# SCH_PCB-BRAILLE_2026-08-12.net
KiCad netlist of a schematic drawn in EasyEDA
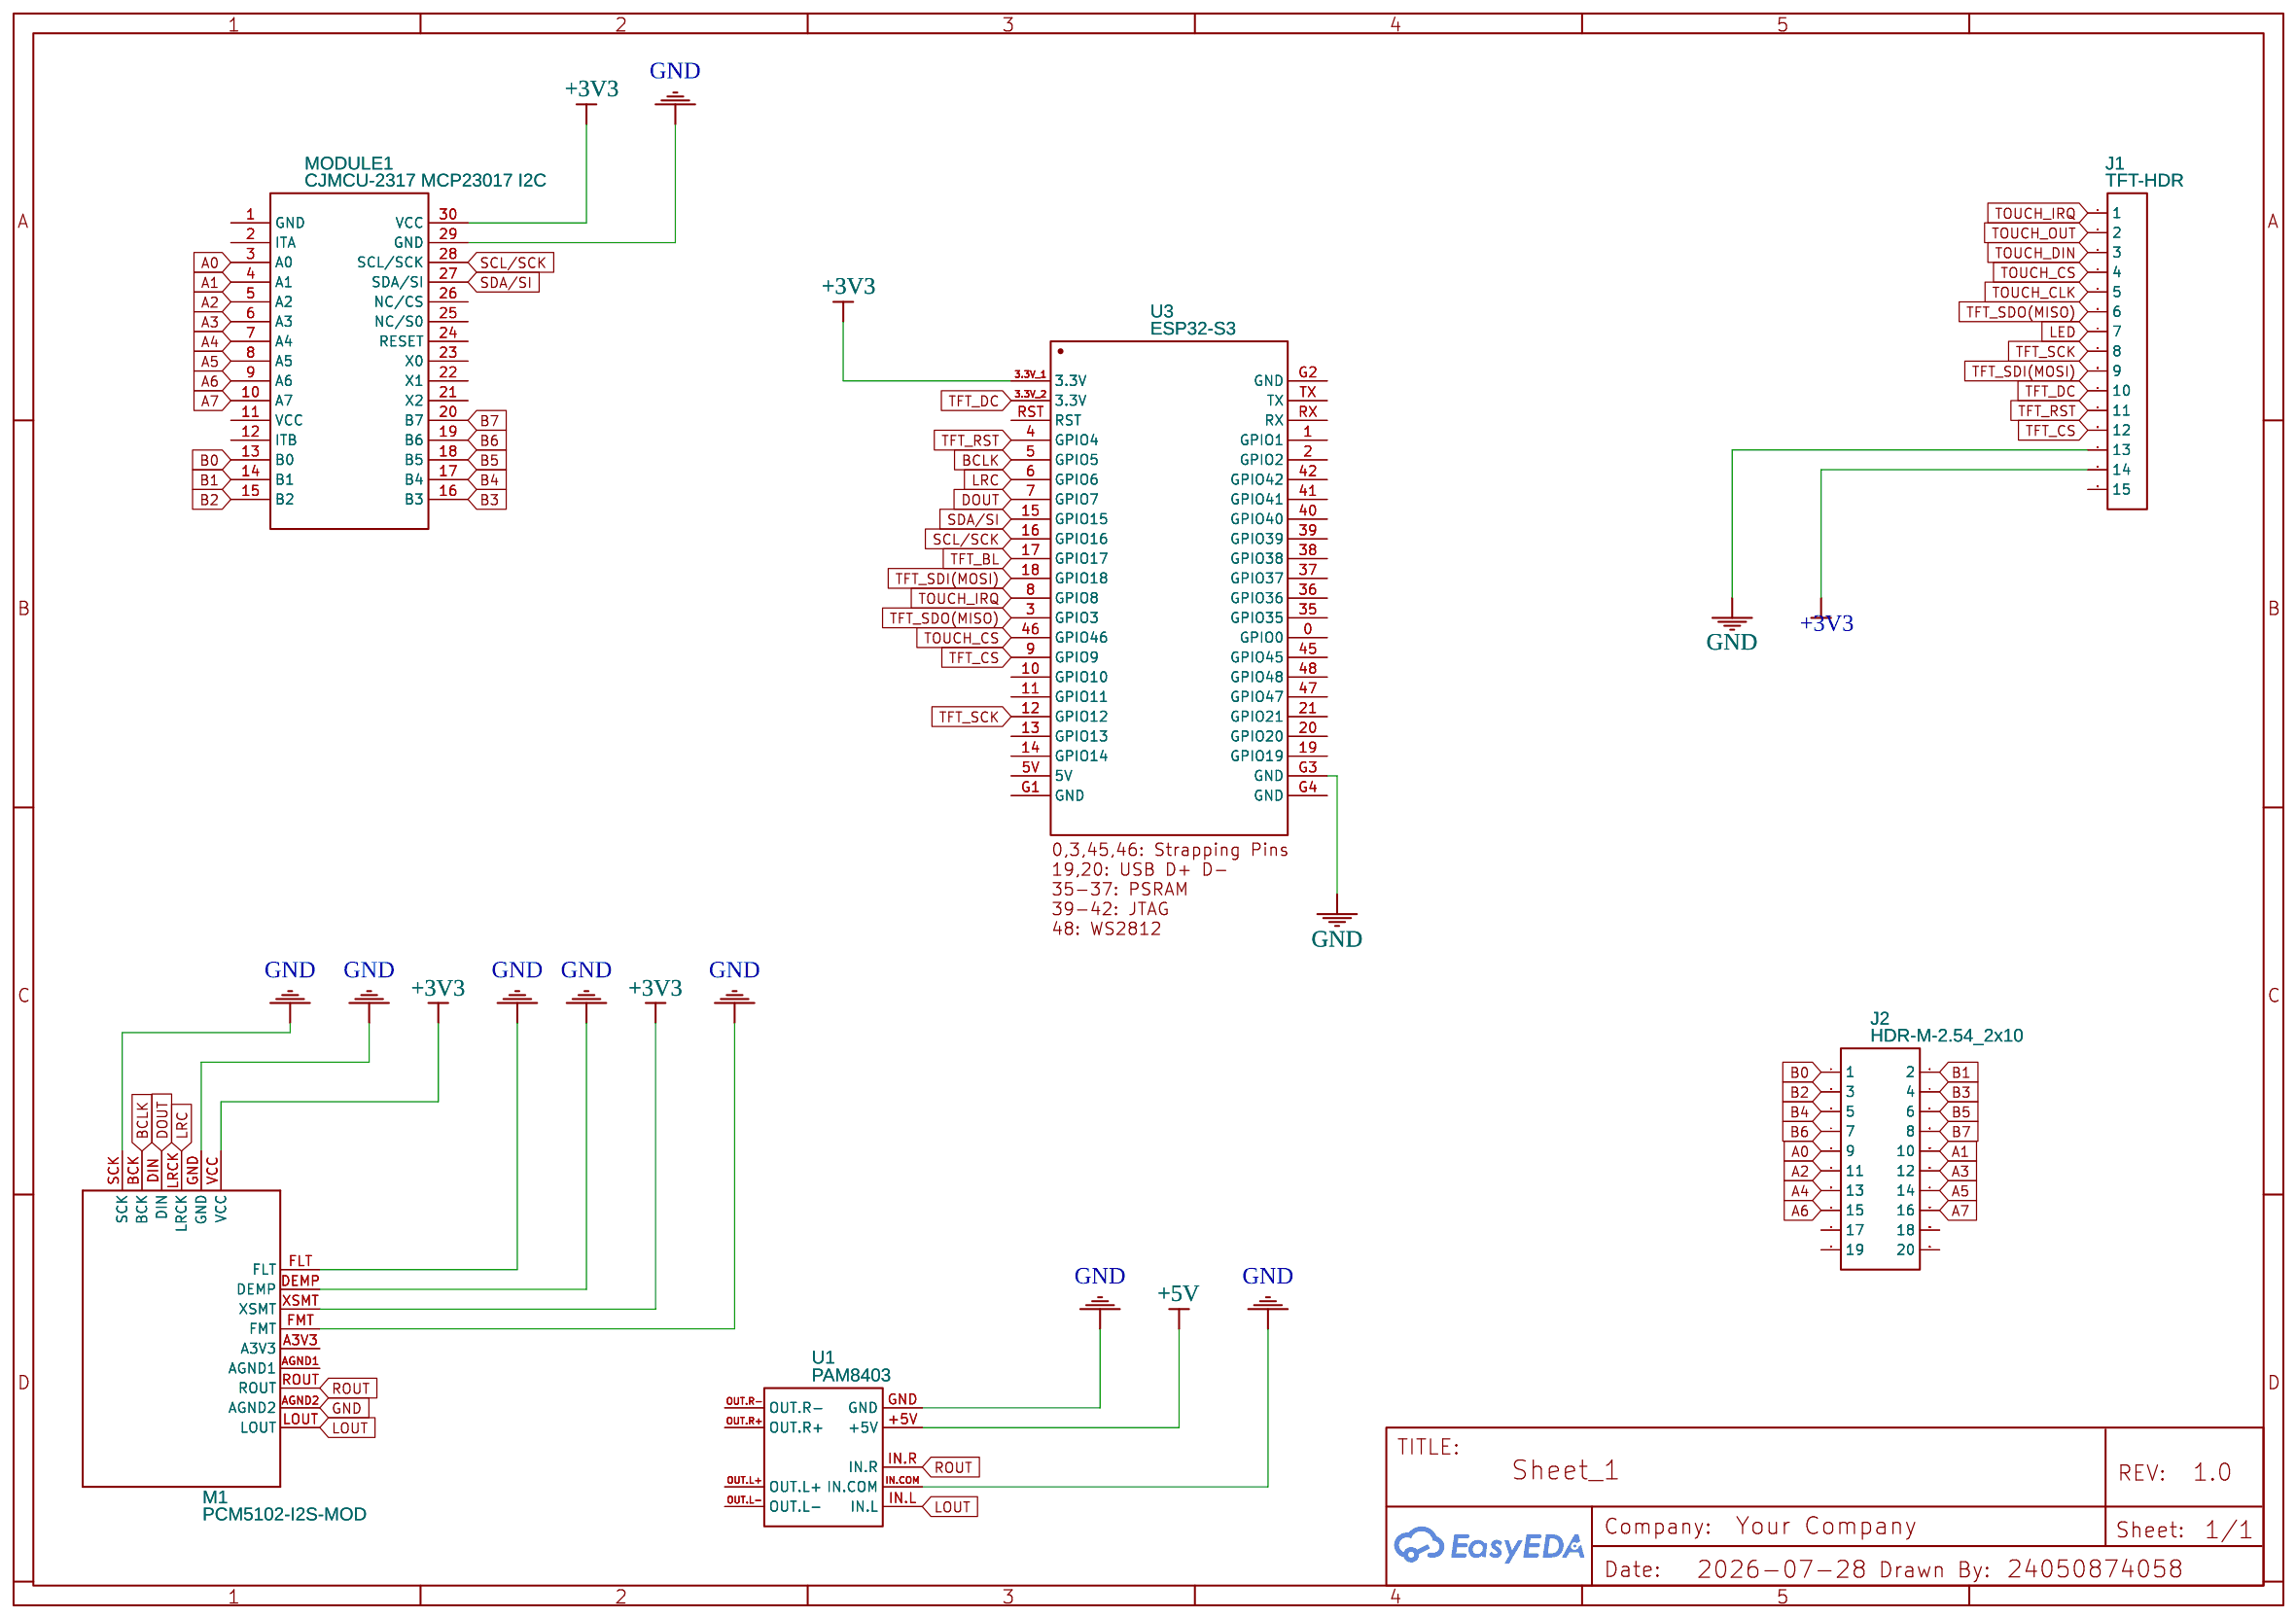
[diagram p0: schematic sheet]

(export (version "E")
  (design (tool "Eeschema 10.0.6"))
  (components
    (comp (ref "J1") (value "TFT-HDR") (libsource (lib "") (part "HDR-M-2.54_1x15")))
    (comp (ref "J2") (value "HDR-M-2.54_2x10") (libsource (lib "") (part "HDR-M-2.54_2x10")))
    (comp (ref "M1") (value "PCM5102-I2S-MOD") (libsource (lib "") (part "PCM5102-I2S-MOD")))
    (comp (ref "MODULE1")
      (value "CJMCU-2317 MCP23017 I2C")
      (libsource (lib "") (part "CJMCU-2317 MCP23017 I2C Serial Interface 16 bit I/O Expander Serial Module"))
    )
    (comp (ref "U1") (value "PAM8403") (libsource (lib "") (part "PAM8403")))
    (comp (ref "U3") (value "ESP32-S3") (libsource (lib "") (part "ESP32-S3")))
  )
  (nets
    (net (code "1") (name "+3V3") (class "Default")
      (node (ref "J1") (pin "14") (pinfunction "14_14") (pintype "unspecified"))
      (node (ref "M1") (pin "VCC") (pinfunction "VCC_VCC") (pintype "bidirectional"))
      (node (ref "M1") (pin "XSMT") (pinfunction "XSMT_XSMT") (pintype "bidirectional"))
      (node (ref "MODULE1") (pin "30") (pinfunction "VCC_30") (pintype "unspecified"))
      (node (ref "U3") (pin "3.3V_1") (pinfunction "3.3V_3.3V_1") (pintype "bidirectional"))
    )
    (net (code "2") (name "+5V") (class "Default")
      (node (ref "U1") (pin "+5V") (pinfunction "+5V_+5V") (pintype "unspecified"))
    )
    (net (code "3") (name "A0") (class "Default")
      (node (ref "J2") (pin "9") (pinfunction "9_9") (pintype "unspecified"))
      (node (ref "MODULE1") (pin "3") (pinfunction "A0_3") (pintype "unspecified"))
    )
    (net (code "4") (name "A1") (class "Default")
      (node (ref "J2") (pin "10") (pinfunction "10_10") (pintype "unspecified"))
      (node (ref "MODULE1") (pin "4") (pinfunction "A1_4") (pintype "unspecified"))
    )
    (net (code "5") (name "A2") (class "Default")
      (node (ref "J2") (pin "11") (pinfunction "11_11") (pintype "unspecified"))
      (node (ref "MODULE1") (pin "5") (pinfunction "A2_5") (pintype "unspecified"))
    )
    (net (code "6") (name "A3") (class "Default")
      (node (ref "J2") (pin "12") (pinfunction "12_12") (pintype "unspecified"))
      (node (ref "MODULE1") (pin "6") (pinfunction "A3_6") (pintype "unspecified"))
    )
    (net (code "7") (name "A4") (class "Default")
      (node (ref "J2") (pin "13") (pinfunction "13_13") (pintype "unspecified"))
      (node (ref "MODULE1") (pin "7") (pinfunction "A4_7") (pintype "unspecified"))
    )
    (net (code "8") (name "A5") (class "Default")
      (node (ref "J2") (pin "14") (pinfunction "14_14") (pintype "unspecified"))
      (node (ref "MODULE1") (pin "8") (pinfunction "A5_8") (pintype "unspecified"))
    )
    (net (code "9") (name "A6") (class "Default")
      (node (ref "J2") (pin "15") (pinfunction "15_15") (pintype "unspecified"))
      (node (ref "MODULE1") (pin "9") (pinfunction "A6_9") (pintype "unspecified"))
    )
    (net (code "10") (name "A7") (class "Default")
      (node (ref "J2") (pin "16") (pinfunction "16_16") (pintype "unspecified"))
      (node (ref "MODULE1") (pin "10") (pinfunction "A7_10") (pintype "unspecified"))
    )
    (net (code "11") (name "B0") (class "Default")
      (node (ref "J2") (pin "1") (pinfunction "1_1") (pintype "unspecified"))
      (node (ref "MODULE1") (pin "13") (pinfunction "B0_13") (pintype "unspecified"))
    )
    (net (code "12") (name "B1") (class "Default")
      (node (ref "J2") (pin "2") (pinfunction "2_2") (pintype "unspecified"))
      (node (ref "MODULE1") (pin "14") (pinfunction "B1_14") (pintype "unspecified"))
    )
    (net (code "13") (name "B2") (class "Default")
      (node (ref "J2") (pin "3") (pinfunction "3_3") (pintype "unspecified"))
      (node (ref "MODULE1") (pin "15") (pinfunction "B2_15") (pintype "unspecified"))
    )
    (net (code "14") (name "B3") (class "Default")
      (node (ref "J2") (pin "4") (pinfunction "4_4") (pintype "unspecified"))
      (node (ref "MODULE1") (pin "16") (pinfunction "B3_16") (pintype "unspecified"))
    )
    (net (code "15") (name "B4") (class "Default")
      (node (ref "J2") (pin "5") (pinfunction "5_5") (pintype "unspecified"))
      (node (ref "MODULE1") (pin "17") (pinfunction "B4_17") (pintype "unspecified"))
    )
    (net (code "16") (name "B5") (class "Default")
      (node (ref "J2") (pin "6") (pinfunction "6_6") (pintype "unspecified"))
      (node (ref "MODULE1") (pin "18") (pinfunction "B5_18") (pintype "unspecified"))
    )
    (net (code "17") (name "B6") (class "Default")
      (node (ref "J2") (pin "7") (pinfunction "7_7") (pintype "unspecified"))
      (node (ref "MODULE1") (pin "19") (pinfunction "B6_19") (pintype "unspecified"))
    )
    (net (code "18") (name "B7") (class "Default")
      (node (ref "J2") (pin "8") (pinfunction "8_8") (pintype "unspecified"))
      (node (ref "MODULE1") (pin "20") (pinfunction "B7_20") (pintype "unspecified"))
    )
    (net (code "19") (name "BCLK") (class "Default")
      (node (ref "M1") (pin "BCK") (pinfunction "BCK_BCK") (pintype "bidirectional"))
      (node (ref "U3") (pin "5") (pinfunction "GPIO5_5") (pintype "bidirectional"))
    )
    (net (code "20") (name "DOUT") (class "Default")
      (node (ref "M1") (pin "DIN") (pinfunction "DIN_DIN") (pintype "bidirectional"))
      (node (ref "U3") (pin "7") (pinfunction "GPIO7_7") (pintype "bidirectional"))
    )
    (net (code "21") (name "GND") (class "Default")
      (node (ref "J1") (pin "13") (pinfunction "13_13") (pintype "unspecified"))
      (node (ref "M1") (pin "AGND2") (pinfunction "AGND2_AGND2") (pintype "bidirectional"))
      (node (ref "M1") (pin "DEMP") (pinfunction "DEMP_DEMP") (pintype "bidirectional"))
      (node (ref "M1") (pin "FLT") (pinfunction "FLT_FLT") (pintype "bidirectional"))
      (node (ref "M1") (pin "FMT") (pinfunction "FMT_FMT") (pintype "bidirectional"))
      (node (ref "M1") (pin "GND") (pinfunction "GND_GND") (pintype "bidirectional"))
      (node (ref "M1") (pin "SCK") (pinfunction "SCK_SCK") (pintype "bidirectional"))
      (node (ref "MODULE1") (pin "29") (pinfunction "GND_29") (pintype "unspecified"))
      (node (ref "U1") (pin "GND") (pinfunction "GND_GND") (pintype "unspecified"))
      (node (ref "U1") (pin "IN.COM") (pinfunction "IN.COM_IN.COM") (pintype "unspecified"))
      (node (ref "U3") (pin "G3") (pinfunction "GND_G3") (pintype "bidirectional"))
    )
    (net (code "22") (name "LED") (class "Default")
      (node (ref "J1") (pin "7") (pinfunction "7_7") (pintype "unspecified"))
    )
    (net (code "23") (name "LOUT") (class "Default")
      (node (ref "M1") (pin "LOUT") (pinfunction "LOUT_LOUT") (pintype "bidirectional"))
      (node (ref "U1") (pin "IN.L") (pinfunction "IN.L_IN.L") (pintype "unspecified"))
    )
    (net (code "24") (name "LRC") (class "Default")
      (node (ref "M1") (pin "LRCK") (pinfunction "LRCK_LRCK") (pintype "bidirectional"))
      (node (ref "U3") (pin "6") (pinfunction "GPIO6_6") (pintype "bidirectional"))
    )
    (net (code "25") (name "ROUT") (class "Default")
      (node (ref "M1") (pin "ROUT") (pinfunction "ROUT_ROUT") (pintype "bidirectional"))
      (node (ref "U1") (pin "IN.R") (pinfunction "IN.R_IN.R") (pintype "unspecified"))
    )
    (net (code "26") (name "SCL{slash}SCK") (class "Default")
      (node (ref "MODULE1") (pin "28") (pinfunction "SCL/SCK_28") (pintype "unspecified"))
      (node (ref "U3") (pin "16") (pinfunction "GPIO16_16") (pintype "bidirectional"))
    )
    (net (code "27") (name "SDA{slash}SI") (class "Default")
      (node (ref "MODULE1") (pin "27") (pinfunction "SDA/SI_27") (pintype "unspecified"))
      (node (ref "U3") (pin "15") (pinfunction "GPIO15_15") (pintype "bidirectional"))
    )
    (net (code "28") (name "TFT_BL") (class "Default")
      (node (ref "U3") (pin "17") (pinfunction "GPIO17_17") (pintype "bidirectional"))
    )
    (net (code "29") (name "TFT_CS") (class "Default")
      (node (ref "J1") (pin "12") (pinfunction "12_12") (pintype "unspecified"))
      (node (ref "U3") (pin "9") (pinfunction "GPIO9_9") (pintype "bidirectional"))
    )
    (net (code "30") (name "TFT_DC") (class "Default")
      (node (ref "J1") (pin "10") (pinfunction "10_10") (pintype "unspecified"))
      (node (ref "U3") (pin "3.3V_2") (pinfunction "3.3V_3.3V_2") (pintype "bidirectional"))
    )
    (net (code "31") (name "TFT_RST") (class "Default")
      (node (ref "J1") (pin "11") (pinfunction "11_11") (pintype "unspecified"))
      (node (ref "U3") (pin "4") (pinfunction "GPIO4_4") (pintype "bidirectional"))
    )
    (net (code "32") (name "TFT_SCK") (class "Default")
      (node (ref "J1") (pin "8") (pinfunction "8_8") (pintype "unspecified"))
      (node (ref "U3") (pin "12") (pinfunction "GPIO12_12") (pintype "bidirectional"))
    )
    (net (code "33") (name "TFT_SDI(MOSI)") (class "Default")
      (node (ref "J1") (pin "9") (pinfunction "9_9") (pintype "unspecified"))
      (node (ref "U3") (pin "18") (pinfunction "GPIO18_18") (pintype "bidirectional"))
    )
    (net (code "34") (name "TFT_SDO(MISO)") (class "Default")
      (node (ref "J1") (pin "6") (pinfunction "6_6") (pintype "unspecified"))
      (node (ref "U3") (pin "3") (pinfunction "GPIO3_3") (pintype "bidirectional"))
    )
    (net (code "35") (name "TOUCH_CLK") (class "Default")
      (node (ref "J1") (pin "5") (pinfunction "5_5") (pintype "unspecified"))
    )
    (net (code "36") (name "TOUCH_CS") (class "Default")
      (node (ref "J1") (pin "4") (pinfunction "4_4") (pintype "unspecified"))
      (node (ref "U3") (pin "46") (pinfunction "GPIO46_46") (pintype "bidirectional"))
    )
    (net (code "37") (name "TOUCH_DIN") (class "Default")
      (node (ref "J1") (pin "3") (pinfunction "3_3") (pintype "unspecified"))
    )
    (net (code "38") (name "TOUCH_IRQ") (class "Default")
      (node (ref "J1") (pin "1") (pinfunction "1_1") (pintype "unspecified"))
      (node (ref "U3") (pin "8") (pinfunction "GPIO8_8") (pintype "bidirectional"))
    )
    (net (code "39") (name "TOUCH_OUT") (class "Default")
      (node (ref "J1") (pin "2") (pinfunction "2_2") (pintype "unspecified"))
    )
    (net (code "40") (name "unconnected-(J1-Pad15)") (class "Default")
      (node (ref "J1") (pin "15") (pinfunction "15_15") (pintype "unspecified"))
    )
    (net (code "41") (name "unconnected-(J2-Pad17)") (class "Default")
      (node (ref "J2") (pin "17") (pinfunction "17_17") (pintype "unspecified"))
    )
    (net (code "42") (name "unconnected-(J2-Pad18)") (class "Default")
      (node (ref "J2") (pin "18") (pinfunction "18_18") (pintype "unspecified"))
    )
    (net (code "43") (name "unconnected-(J2-Pad19)") (class "Default")
      (node (ref "J2") (pin "19") (pinfunction "19_19") (pintype "unspecified"))
    )
    (net (code "44") (name "unconnected-(J2-Pad20)") (class "Default")
      (node (ref "J2") (pin "20") (pinfunction "20_20") (pintype "unspecified"))
    )
    (net (code "45") (name "unconnected-(M1-PadA3V3)") (class "Default")
      (node (ref "M1") (pin "A3V3") (pinfunction "A3V3_A3V3") (pintype "bidirectional"))
    )
    (net (code "46") (name "unconnected-(M1-PadAGND1)") (class "Default")
      (node (ref "M1") (pin "AGND1") (pinfunction "AGND1_AGND1") (pintype "bidirectional"))
    )
    (net (code "47") (name "unconnected-(MODULE1-GND-Pad1)") (class "Default")
      (node (ref "MODULE1") (pin "1") (pinfunction "GND_1") (pintype "unspecified"))
    )
    (net (code "48") (name "unconnected-(MODULE1-ITA-Pad2)") (class "Default")
      (node (ref "MODULE1") (pin "2") (pinfunction "ITA_2") (pintype "unspecified"))
    )
    (net (code "49") (name "unconnected-(MODULE1-ITB-Pad12)") (class "Default")
      (node (ref "MODULE1") (pin "12") (pinfunction "ITB_12") (pintype "unspecified"))
    )
    (net (code "50") (name "unconnected-(MODULE1-NC{slash}CS-Pad26)") (class "Default")
      (node (ref "MODULE1") (pin "26") (pinfunction "NC/CS_26") (pintype "unspecified"))
    )
    (net (code "51") (name "unconnected-(MODULE1-NC{slash}S0-Pad25)") (class "Default")
      (node (ref "MODULE1") (pin "25") (pinfunction "NC/S0_25") (pintype "unspecified"))
    )
    (net (code "52") (name "unconnected-(MODULE1-RESET-Pad24)") (class "Default")
      (node (ref "MODULE1") (pin "24") (pinfunction "RESET_24") (pintype "unspecified"))
    )
    (net (code "53") (name "unconnected-(MODULE1-VCC-Pad11)") (class "Default")
      (node (ref "MODULE1") (pin "11") (pinfunction "VCC_11") (pintype "unspecified"))
    )
    (net (code "54") (name "unconnected-(MODULE1-X0-Pad23)") (class "Default")
      (node (ref "MODULE1") (pin "23") (pinfunction "X0_23") (pintype "unspecified"))
    )
    (net (code "55") (name "unconnected-(MODULE1-X1-Pad22)") (class "Default")
      (node (ref "MODULE1") (pin "22") (pinfunction "X1_22") (pintype "unspecified"))
    )
    (net (code "56") (name "unconnected-(MODULE1-X2-Pad21)") (class "Default")
      (node (ref "MODULE1") (pin "21") (pinfunction "X2_21") (pintype "unspecified"))
    )
    (net (code "57") (name "unconnected-(U1-PadOUT.L+)") (class "Default")
      (node (ref "U1") (pin "OUT.L+") (pinfunction "OUT.L+_OUT.L+") (pintype "unspecified"))
    )
    (net (code "58") (name "unconnected-(U1-PadOUT.L-)") (class "Default")
      (node (ref "U1") (pin "OUT.L-") (pinfunction "OUT.L-_OUT.L-") (pintype "unspecified"))
    )
    (net (code "59") (name "unconnected-(U1-PadOUT.R+)") (class "Default")
      (node (ref "U1") (pin "OUT.R+") (pinfunction "OUT.R+_OUT.R+") (pintype "unspecified"))
    )
    (net (code "60") (name "unconnected-(U1-PadOUT.R-)") (class "Default")
      (node (ref "U1") (pin "OUT.R-") (pinfunction "OUT.R-_OUT.R-") (pintype "unspecified"))
    )
    (net (code "61") (name "unconnected-(U3-GND-PadG1)") (class "Default")
      (node (ref "U3") (pin "G1") (pinfunction "GND_G1") (pintype "bidirectional"))
    )
    (net (code "62") (name "unconnected-(U3-GND-PadG2)") (class "Default")
      (node (ref "U3") (pin "G2") (pinfunction "GND_G2") (pintype "bidirectional"))
    )
    (net (code "63") (name "unconnected-(U3-GND-PadG4)") (class "Default")
      (node (ref "U3") (pin "G4") (pinfunction "GND_G4") (pintype "bidirectional"))
    )
    (net (code "64") (name "unconnected-(U3-GPIO0-Pad0)") (class "Default")
      (node (ref "U3") (pin "0") (pinfunction "GPIO0_0") (pintype "bidirectional"))
    )
    (net (code "65") (name "unconnected-(U3-GPIO1-Pad1)") (class "Default")
      (node (ref "U3") (pin "1") (pinfunction "GPIO1_1") (pintype "bidirectional"))
    )
    (net (code "66") (name "unconnected-(U3-GPIO2-Pad2)") (class "Default")
      (node (ref "U3") (pin "2") (pinfunction "GPIO2_2") (pintype "bidirectional"))
    )
    (net (code "67") (name "unconnected-(U3-GPIO10-Pad10)") (class "Default")
      (node (ref "U3") (pin "10") (pinfunction "GPIO10_10") (pintype "bidirectional"))
    )
    (net (code "68") (name "unconnected-(U3-GPIO11-Pad11)") (class "Default")
      (node (ref "U3") (pin "11") (pinfunction "GPIO11_11") (pintype "bidirectional"))
    )
    (net (code "69") (name "unconnected-(U3-GPIO13-Pad13)") (class "Default")
      (node (ref "U3") (pin "13") (pinfunction "GPIO13_13") (pintype "bidirectional"))
    )
    (net (code "70") (name "unconnected-(U3-GPIO14-Pad14)") (class "Default")
      (node (ref "U3") (pin "14") (pinfunction "GPIO14_14") (pintype "bidirectional"))
    )
    (net (code "71") (name "unconnected-(U3-GPIO19-Pad19)") (class "Default")
      (node (ref "U3") (pin "19") (pinfunction "GPIO19_19") (pintype "bidirectional"))
    )
    (net (code "72") (name "unconnected-(U3-GPIO20-Pad20)") (class "Default")
      (node (ref "U3") (pin "20") (pinfunction "GPIO20_20") (pintype "bidirectional"))
    )
    (net (code "73") (name "unconnected-(U3-GPIO21-Pad21)") (class "Default")
      (node (ref "U3") (pin "21") (pinfunction "GPIO21_21") (pintype "bidirectional"))
    )
    (net (code "74") (name "unconnected-(U3-GPIO35-Pad35)") (class "Default")
      (node (ref "U3") (pin "35") (pinfunction "GPIO35_35") (pintype "bidirectional"))
    )
    (net (code "75") (name "unconnected-(U3-GPIO36-Pad36)") (class "Default")
      (node (ref "U3") (pin "36") (pinfunction "GPIO36_36") (pintype "bidirectional"))
    )
    (net (code "76") (name "unconnected-(U3-GPIO37-Pad37)") (class "Default")
      (node (ref "U3") (pin "37") (pinfunction "GPIO37_37") (pintype "bidirectional"))
    )
    (net (code "77") (name "unconnected-(U3-GPIO38-Pad38)") (class "Default")
      (node (ref "U3") (pin "38") (pinfunction "GPIO38_38") (pintype "bidirectional"))
    )
    (net (code "78") (name "unconnected-(U3-GPIO39-Pad39)") (class "Default")
      (node (ref "U3") (pin "39") (pinfunction "GPIO39_39") (pintype "bidirectional"))
    )
    (net (code "79") (name "unconnected-(U3-GPIO40-Pad40)") (class "Default")
      (node (ref "U3") (pin "40") (pinfunction "GPIO40_40") (pintype "bidirectional"))
    )
    (net (code "80") (name "unconnected-(U3-GPIO41-Pad41)") (class "Default")
      (node (ref "U3") (pin "41") (pinfunction "GPIO41_41") (pintype "bidirectional"))
    )
    (net (code "81") (name "unconnected-(U3-GPIO42-Pad42)") (class "Default")
      (node (ref "U3") (pin "42") (pinfunction "GPIO42_42") (pintype "bidirectional"))
    )
    (net (code "82") (name "unconnected-(U3-GPIO45-Pad45)") (class "Default")
      (node (ref "U3") (pin "45") (pinfunction "GPIO45_45") (pintype "bidirectional"))
    )
    (net (code "83") (name "unconnected-(U3-GPIO47-Pad47)") (class "Default")
      (node (ref "U3") (pin "47") (pinfunction "GPIO47_47") (pintype "bidirectional"))
    )
    (net (code "84") (name "unconnected-(U3-GPIO48-Pad48)") (class "Default")
      (node (ref "U3") (pin "48") (pinfunction "GPIO48_48") (pintype "bidirectional"))
    )
    (net (code "85") (name "unconnected-(U3-Pad5V)") (class "Default")
      (node (ref "U3") (pin "5V") (pinfunction "5V_5V") (pintype "bidirectional"))
    )
    (net (code "86") (name "unconnected-(U3-PadRST)") (class "Default")
      (node (ref "U3") (pin "RST") (pinfunction "RST_RST") (pintype "bidirectional"))
    )
    (net (code "87") (name "unconnected-(U3-PadRX)") (class "Default")
      (node (ref "U3") (pin "RX") (pinfunction "RX_RX") (pintype "bidirectional"))
    )
    (net (code "88") (name "unconnected-(U3-PadTX)") (class "Default")
      (node (ref "U3") (pin "TX") (pinfunction "TX_TX") (pintype "bidirectional"))
    )
  )
)
